# 3_Charging.net
KiCad netlist of a schematic drawn in Altium Designer
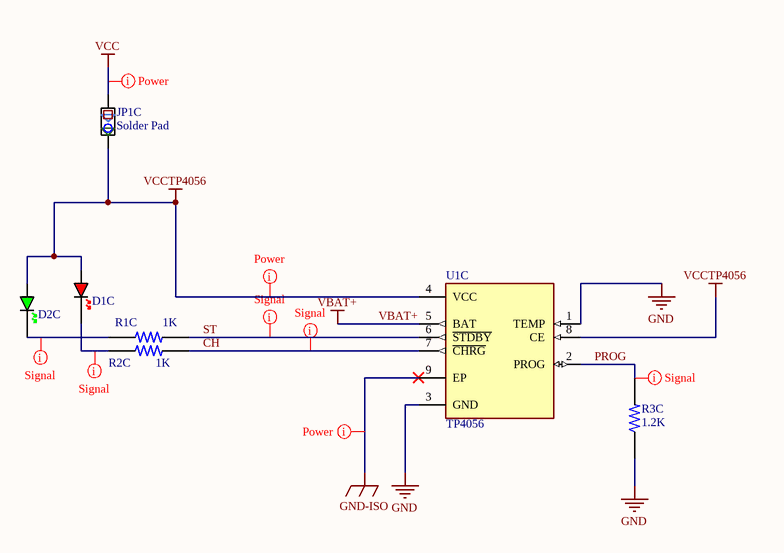
[diagram p0: 3_Charging.SchDoc]

(export (version "E")
  (design (tool "Eeschema 10.0.6"))
  (components
    (comp (ref "D1C")
      (value "RED")
      (footprint "LED_0603_RED")
      (description "LED 0603 RED SMD")
      (libsource (lib "ESP-12F_WLED_IOT_LIPO") (part "LED_0603_RED"))
    )
    (comp (ref "D2C")
      (value "GREEN")
      (footprint "LED_0603_GREEN")
      (description "LED 0603 GREEN SMD")
      (libsource (lib "ESP-12F_WLED_IOT_LIPO") (part "LED_0603_GREEN"))
    )
    (comp (ref "JP1C")
      (value "Solder Pad")
      (footprint "Solder_Pad_2_Pin_NC_Medium")
      (description "Solder Pad 2 Pin NC 1.016 mm Pitch")
      (libsource (lib "ESP-12F_WLED_IOT_LIPO") (part "Solder_Pad_2_Pin_NC_Medium"))
    )
    (comp (ref "R1C")
      (value "1K")
      (footprint "R-0603")
      (description "0603")
      (fields (field (name "MP") "2-1623703-0") (field (name "TOLERANCE") "1%"))
      (libsource (lib "ESP-12F_WLED_IOT_LIPO") (part "R-0603"))
    )
    (comp (ref "R2C")
      (value "1K")
      (footprint "R-0603")
      (description "0603")
      (fields (field (name "MP") "2-1623703-0") (field (name "TOLERANCE") "1%"))
      (libsource (lib "ESP-12F_WLED_IOT_LIPO") (part "R-0603"))
    )
    (comp (ref "R3C")
      (value "1.2K")
      (footprint "R-0603")
      (description "0603")
      (fields (field (name "MP") "2-1623703-0") (field (name "TOLERANCE") "1%"))
      (libsource (lib "ESP-12F_WLED_IOT_LIPO") (part "R-0603"))
    )
    (comp (ref "U1C")
      (value "TP4056")
      (footprint "TP4056")
      (description "Complete single cell Li-Ion battery with a constant current / constant voltage linear charger")
      (libsource (lib "ESP-12F_WLED_IOT_LIPO") (part "TP4056"))
    )
  )
  (nets
    (net (code "1") (name "/CH") (class "Default")
      (node (ref "R2C") (pin "2") (pinfunction "2_2") (pintype "passive"))
      (node (ref "U1C") (pin "7") (pinfunction "~{CHRG}_7") (pintype "output"))
    )
    (net (code "2") (name "/PROG") (class "Default")
      (node (ref "R3C") (pin "2") (pinfunction "2_2") (pintype "passive"))
      (node (ref "U1C") (pin "2") (pinfunction "PROG_2") (pintype "bidirectional"))
    )
    (net (code "3") (name "/ST") (class "Default")
      (node (ref "R1C") (pin "2") (pinfunction "2_2") (pintype "passive"))
      (node (ref "U1C") (pin "6") (pinfunction "~{STDBY}_6") (pintype "output"))
    )
    (net (code "4") (name "GND") (class "Default")
      (node (ref "R3C") (pin "1") (pinfunction "1_1") (pintype "passive"))
      (node (ref "U1C") (pin "1") (pinfunction "TEMP_1") (pintype "input"))
      (node (ref "U1C") (pin "3") (pinfunction "GND_3") (pintype "power_in"))
    )
    (net (code "5") (name "GND-ISO") (class "Default")
      (node (ref "U1C") (pin "9") (pinfunction "EP_9") (pintype "passive"))
    )
    (net (code "6") (name "Net-(D1C-PadK)") (class "Default")
      (node (ref "D1C") (pin "K") (pinfunction "K_K") (pintype "passive"))
      (node (ref "R2C") (pin "1") (pinfunction "1_1") (pintype "passive"))
    )
    (net (code "7") (name "Net-(D2C-PadK)") (class "Default")
      (node (ref "D2C") (pin "K") (pinfunction "K_K") (pintype "passive"))
      (node (ref "R1C") (pin "1") (pinfunction "1_1") (pintype "passive"))
    )
    (net (code "8") (name "VBAT+") (class "Default")
      (node (ref "U1C") (pin "5") (pinfunction "BAT_5") (pintype "output"))
    )
    (net (code "9") (name "VCC") (class "Default")
      (node (ref "JP1C") (pin "1") (pinfunction "1_1") (pintype "passive"))
    )
    (net (code "10") (name "VCCTP4056") (class "Default")
      (node (ref "D1C") (pin "A") (pinfunction "A_A") (pintype "passive"))
      (node (ref "D2C") (pin "A") (pinfunction "A_A") (pintype "passive"))
      (node (ref "JP1C") (pin "2") (pinfunction "2_2") (pintype "passive"))
      (node (ref "U1C") (pin "4") (pinfunction "VCC_4") (pintype "power_in"))
      (node (ref "U1C") (pin "8") (pinfunction "CE_8") (pintype "input"))
    )
  )
)
